# CC_oct_driver.net
KiCad netlist of a schematic drawn in Altium Designer
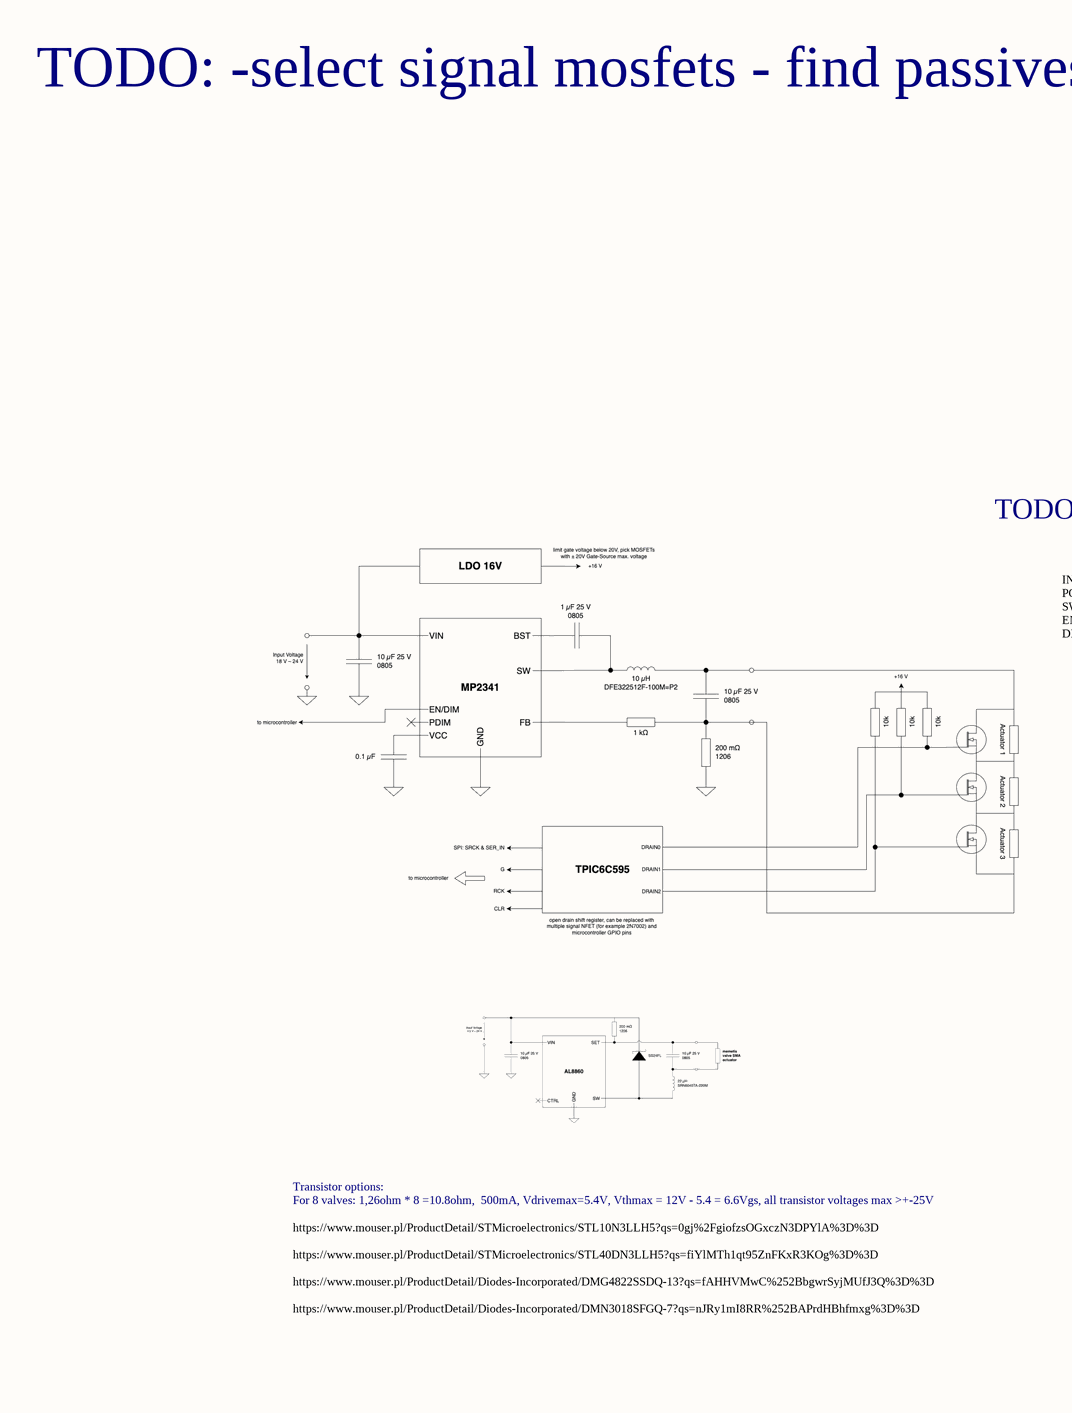
[diagram p0: CC_oct_driver.SchDoc, left]
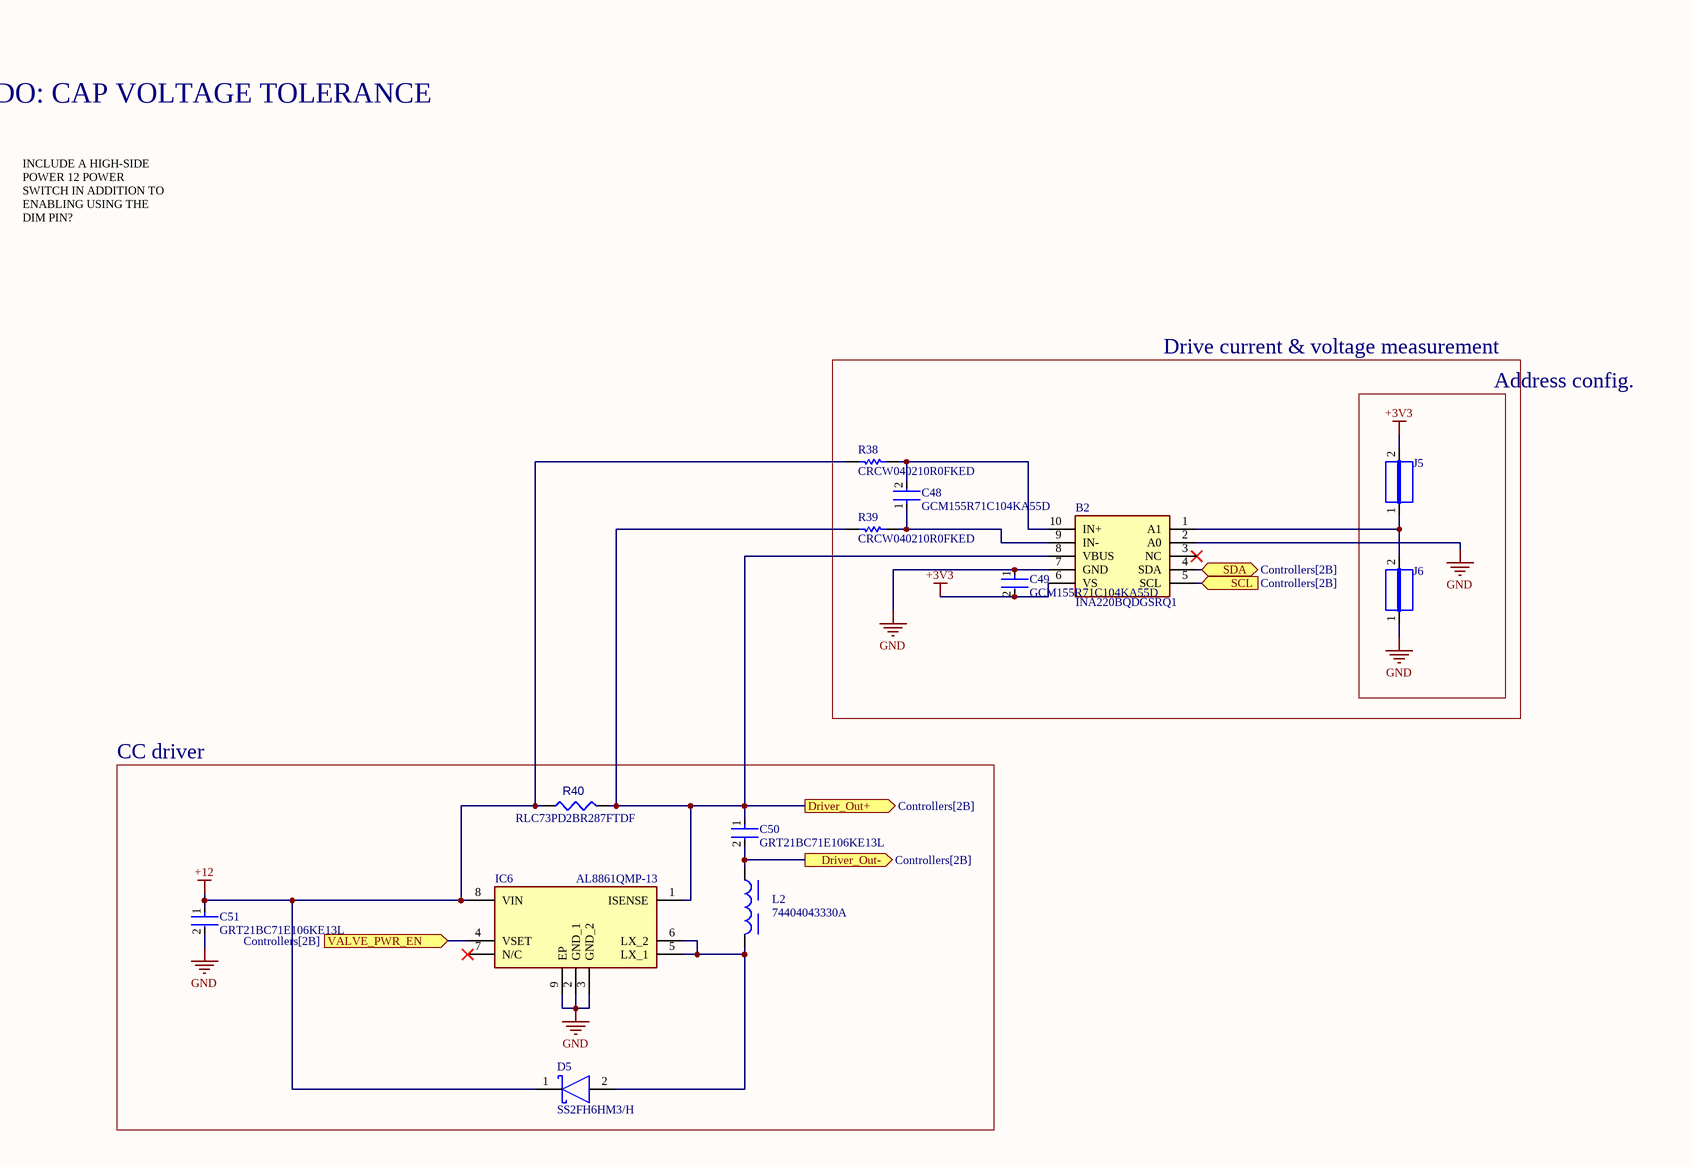
[diagram p1: CC_oct_driver.SchDoc, right]

(export (version "E")
  (design (tool "Eeschema 10.0.6"))
  (components
    (comp (ref "B2")
      (value "INA220BQDGSRQ1")
      (footprint "SOP50P490X110-10N")
      (description "Automotive, 26-V, Bi-Directional, Zero-Drift, Low-/High-Side, I2C Out Current/Power Monitor")
      (fields (field (name "MOUSER PART NUMBER") "595-INA220BQDGSRQ1"))
      (libsource (lib "INA220BQDGSRQ1") (part "INA220BQDGSRQ1"))
    )
    (comp (ref "C48")
      (value "GCM155R71C104KA55D")
      (footprint "FP-GCM155-0_05-IPC_C")
      (description "Ceramic Capacitor for Automotive 100nF ±10% 16VDC X7R 0402 Paper T/R")
      (fields (field (name "VOLTAGE") "16V") (field (name "TOLERANCE") "10%"))
      (libsource (lib "Altium Content Vault") (part "02cd4be3c70576c341d710602a673aa"))
    )
    (comp (ref "C49")
      (value "GCM155R71C104KA55D")
      (footprint "FP-GCM155-0_05-IPC_C")
      (description "Ceramic Capacitor for Automotive 100nF ±10% 16VDC X7R 0402 Paper T/R")
      (fields (field (name "VOLTAGE") "16V") (field (name "TOLERANCE") "10%"))
      (libsource (lib "Altium Content Vault") (part "02cd4be3c70576c341d710602a673aa"))
    )
    (comp (ref "C50")
      (value "GRT21BC71E106KE13L")
      (footprint "FP-GRT21B-0_2-IPC_B")
      (description "Multi-Layer Ceramic Capacitor 10uF 25V X7S ±10% 0805 Emboss T/R")
      (libsource (lib "Altium Content Vault") (part "02cd4be3c70576c341d710602a673aa"))
    )
    (comp (ref "C51")
      (value "GRT21BC71E106KE13L")
      (footprint "FP-GRT21B-0_2-IPC_B")
      (description "Multi-Layer Ceramic Capacitor 10uF 25V X7S ±10% 0805 Emboss T/R")
      (libsource (lib "Altium Content Vault") (part "02cd4be3c70576c341d710602a673aa"))
    )
    (comp (ref "D5")
      (value "SS2FH6HM3/H")
      (footprint "FP-S8-V-3915_01-001-MFG")
      (description "SS2FH6HM3/H Diode Schottky 60V 2A Automotive 2-Pin SMF T/R")
      (libsource (lib "Altium Content Vault") (part "a071e5edd1fb65b81e22f681b9e141c"))
    )
    (comp (ref "IC6")
      (value "AL8861QMP-13")
      (footprint "SOP65P490X110-9N")
      (description "LED Lighting Drivers LED MV Int Switch MSOP-8EP T&R 2.5K")
      (fields (field (name "MOUSER PART NUMBER") "621-AL8861QMP-13"))
      (libsource (lib "AL8861QMP-13") (part "AL8861QMP-13"))
    )
    (comp (ref "J5")
      (value "JUMPER")
      (footprint "JUMPER")
      (libsource (lib "Piotr Słonka - priv") (part "JUMPER"))
    )
    (comp (ref "J6")
      (value "JUMPER")
      (footprint "JUMPER")
      (libsource (lib "Piotr Słonka - priv") (part "JUMPER"))
    )
    (comp (ref "L2")
      (value "74404043330A")
      (footprint "WE-LQS_4025")
      (description "74404043330A WE-LQS SMT Semi-Shielded Power Inductor")
      (libsource (lib "Altium Content Vault") (part "Inductor - 3"))
    )
    (comp (ref "R38")
      (value "CRCW040210R0FKED")
      (footprint "RESC1005X40X25NL05T05")
      (fields (field (name "MANUFACTURER") "Vishay Dale"))
      (libsource (lib "Altium Content Vault") (part "RES"))
    )
    (comp (ref "R39")
      (value "CRCW040210R0FKED")
      (footprint "RESC1005X40X25NL05T05")
      (fields (field (name "MANUFACTURER") "Vishay Dale"))
      (libsource (lib "Altium Content Vault") (part "RES"))
    )
    (comp (ref "R40")
      (value "RLC73PD2BR287FTDF")
      (footprint "R1206")
      (description "Resistor")
      (libsource (lib "Symbols_AGH_SS") (part "Resistor"))
    )
  )
  (nets
    (net (code "1") (name "+3V3") (class "Default")
      (node (ref "B2") (pin "6") (pinfunction "VS_6") (pintype "passive"))
      (node (ref "C49") (pin "2") (pinfunction "2_2") (pintype "passive"))
      (node (ref "J5") (pin "2") (pinfunction "2_2") (pintype "passive"))
    )
    (net (code "2") (name "+12") (class "Default")
      (node (ref "C51") (pin "1") (pinfunction "1_1") (pintype "passive"))
      (node (ref "D5") (pin "1") (pinfunction "C_1") (pintype "passive"))
      (node (ref "IC6") (pin "8") (pinfunction "VIN_8") (pintype "passive"))
      (node (ref "R38") (pin "1") (pinfunction "1_1") (pintype "passive"))
      (node (ref "R40") (pin "1") (pinfunction "1_1") (pintype "passive"))
    )
    (net (code "3") (name "/Driver_Out+") (class "Default")
      (node (ref "B2") (pin "8") (pinfunction "VBUS_8") (pintype "passive"))
      (node (ref "C50") (pin "1") (pinfunction "1_1") (pintype "passive"))
      (node (ref "IC6") (pin "1") (pinfunction "ISENSE_1") (pintype "passive"))
      (node (ref "R39") (pin "1") (pinfunction "1_1") (pintype "passive"))
      (node (ref "R40") (pin "2") (pinfunction "2_2") (pintype "passive"))
    )
    (net (code "4") (name "/Driver_Out-") (class "Default")
      (node (ref "C50") (pin "2") (pinfunction "2_2") (pintype "passive"))
      (node (ref "L2") (pin "1") (pinfunction "1_1") (pintype "passive"))
    )
    (net (code "5") (name "/SCL") (class "Default")
      (node (ref "B2") (pin "5") (pinfunction "SCL_5") (pintype "passive"))
    )
    (net (code "6") (name "/SDA") (class "Default")
      (node (ref "B2") (pin "4") (pinfunction "SDA_4") (pintype "passive"))
    )
    (net (code "7") (name "/VALVE_PWR_EN") (class "Default")
      (node (ref "IC6") (pin "4") (pinfunction "VSET_4") (pintype "passive"))
    )
    (net (code "8") (name "GND") (class "Default")
      (node (ref "B2") (pin "2") (pinfunction "A0_2") (pintype "passive"))
      (node (ref "B2") (pin "7") (pinfunction "GND_7") (pintype "passive"))
      (node (ref "C49") (pin "1") (pinfunction "1_1") (pintype "passive"))
      (node (ref "C51") (pin "2") (pinfunction "2_2") (pintype "passive"))
      (node (ref "IC6") (pin "2") (pinfunction "GND_1_2") (pintype "passive"))
      (node (ref "IC6") (pin "3") (pinfunction "GND_2_3") (pintype "passive"))
      (node (ref "IC6") (pin "9") (pinfunction "EP_9") (pintype "passive"))
      (node (ref "J6") (pin "1") (pinfunction "1_1") (pintype "passive"))
    )
    (net (code "9") (name "Net-(B2-A1)") (class "Default")
      (node (ref "B2") (pin "1") (pinfunction "A1_1") (pintype "passive"))
      (node (ref "J5") (pin "1") (pinfunction "1_1") (pintype "passive"))
      (node (ref "J6") (pin "2") (pinfunction "2_2") (pintype "passive"))
    )
    (net (code "10") (name "Net-(B2-IN+)") (class "Default")
      (node (ref "B2") (pin "10") (pinfunction "IN+_10") (pintype "passive"))
      (node (ref "C48") (pin "2") (pinfunction "2_2") (pintype "passive"))
      (node (ref "R38") (pin "2") (pinfunction "2_2") (pintype "passive"))
    )
    (net (code "11") (name "Net-(B2-IN-)") (class "Default")
      (node (ref "B2") (pin "9") (pinfunction "IN-_9") (pintype "passive"))
      (node (ref "C48") (pin "1") (pinfunction "1_1") (pintype "passive"))
      (node (ref "R39") (pin "2") (pinfunction "2_2") (pintype "passive"))
    )
    (net (code "12") (name "Net-(D5-A)") (class "Default")
      (node (ref "D5") (pin "2") (pinfunction "A_2") (pintype "passive"))
      (node (ref "IC6") (pin "5") (pinfunction "LX_1_5") (pintype "passive"))
      (node (ref "IC6") (pin "6") (pinfunction "LX_2_6") (pintype "passive"))
      (node (ref "L2") (pin "2") (pinfunction "2_2") (pintype "passive"))
    )
    (net (code "13") (name "unconnected-(B2-NC-Pad3)") (class "Default")
      (node (ref "B2") (pin "3") (pinfunction "NC_3") (pintype "passive+no_connect"))
    )
    (net (code "14") (name "unconnected-(IC6-N{slash}C-Pad7)") (class "Default")
      (node (ref "IC6") (pin "7") (pinfunction "N/C_7") (pintype "passive+no_connect"))
    )
  )
)
